# isolated_rs485.net
KiCad netlist of a schematic drawn in Altium Designer
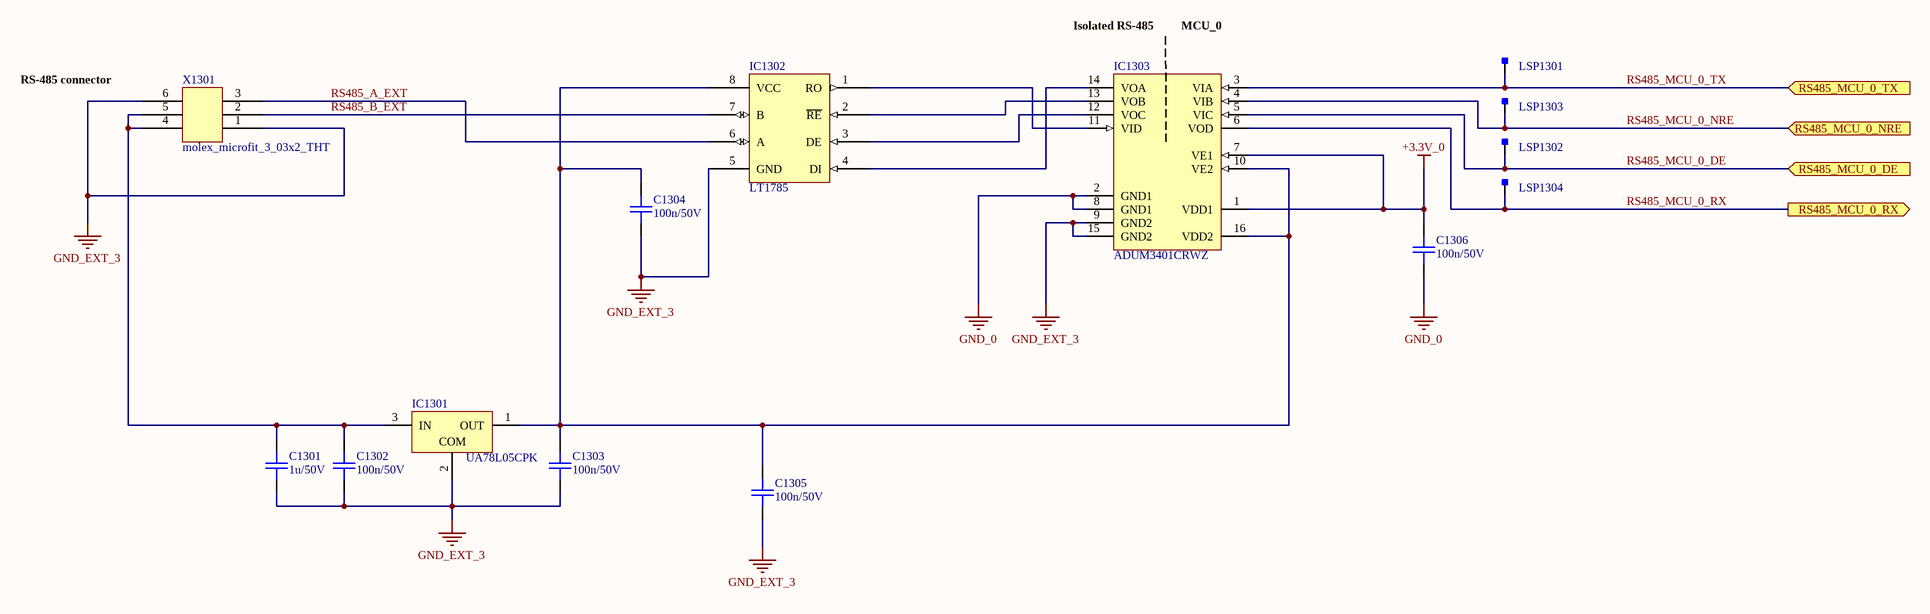
[diagram p0: isolated_rs485.SchDoc]

(export (version "E")
  (design (tool "Eeschema 10.0.6"))
  (components
    (comp (ref "C1301")
      (value "1u/50V")
      (footprint "CAPC1608X08N")
      (description "MLCC")
      (fields (field (name "PART NUMBER") "gen_C_ceramic_1u_50V_X7R_0603") (field (name "TOLERANCE") "± 10%"))
      (libsource (lib "OE750") (part "C"))
    )
    (comp (ref "C1302")
      (value "100n/50V")
      (footprint "CAPC1608X08N")
      (description "MLCC")
      (fields (field (name "PART NUMBER") "gen_C_ceramic_100n_50V_X7R_0603"))
      (libsource (lib "OE750") (part "C"))
    )
    (comp (ref "C1303")
      (value "100n/50V")
      (footprint "CAPC1608X08N")
      (description "MLCC")
      (fields (field (name "PART NUMBER") "gen_C_ceramic_100n_50V_X7R_0603"))
      (libsource (lib "OE750") (part "C"))
    )
    (comp (ref "C1304")
      (value "100n/50V")
      (footprint "CAPC1608X08N")
      (description "MLCC")
      (fields (field (name "PART NUMBER") "gen_C_ceramic_100n_50V_X7R_0603"))
      (libsource (lib "OE750") (part "C"))
    )
    (comp (ref "C1305")
      (value "100n/50V")
      (footprint "CAPC1608X08N")
      (description "MLCC")
      (fields (field (name "PART NUMBER") "gen_C_ceramic_100n_50V_X7R_0603"))
      (libsource (lib "OE750") (part "C"))
    )
    (comp (ref "C1306")
      (value "100n/50V")
      (footprint "CAPC1608X08N")
      (description "MLCC")
      (fields (field (name "PART NUMBER") "gen_C_ceramic_100n_50V_X7R_0603"))
      (libsource (lib "OE750") (part "C"))
    )
    (comp (ref "IC1301")
      (value "UA78L05CPK")
      (footprint "PK0003A_L")
      (fields (field (name "MANUFACTURER") "TexasInstruments"))
      (libsource (lib "Altium Content Vault") (part "TI-UA78L05-PK-3"))
    )
    (comp (ref "IC1302")
      (value "LT1785")
      (footprint "SOIC127P600X175-8N")
      (description "Transceiver RS422/RS485, Fault Protected, 4.75V-5.25V supply, SOIC-8")
      (fields (field (name "PART NUMBER") "LT1785CS8#PBF") (field (name "MANUFACTURER") "Linear Technology"))
      (libsource (lib "OE750") (part "LT1785"))
    )
    (comp (ref "IC1303")
      (value "ADUM3401CRWZ")
      (footprint "ADI-RW-16_N")
      (fields (field (name "MANUFACTURER") "Analog Devices"))
      (libsource (lib "Altium Content Vault") (part "ADI-ADUMX4X1-16"))
    )
    (comp (ref "LSP1301")
      (value "Testpoint_Square")
      (footprint "Testpoint_S1")
      (description "Testpoint, square")
      (libsource (lib "OE750") (part "Testpoint_Square"))
    )
    (comp (ref "LSP1302")
      (value "Testpoint_Square")
      (footprint "Testpoint_S1")
      (description "Testpoint, square")
      (libsource (lib "OE750") (part "Testpoint_Square"))
    )
    (comp (ref "LSP1303")
      (value "Testpoint_Square")
      (footprint "Testpoint_S1")
      (description "Testpoint, square")
      (libsource (lib "OE750") (part "Testpoint_Square"))
    )
    (comp (ref "LSP1304")
      (value "Testpoint_Square")
      (footprint "Testpoint_S1")
      (description "Testpoint, square")
      (libsource (lib "OE750") (part "Testpoint_Square"))
    )
    (comp (ref "X1301")
      (value "molex_microfit_3_03x2_THT")
      (footprint "MOLEX_MICROFIT_03x2_THT")
      (fields (field (name "MANUFACTURER") "Molex"))
      (libsource (lib "OE750") (part "X3x2"))
    )
  )
  (nets
    (net (code "1") (name "+3.3V_0") (class "Default")
      (node (ref "C1306") (pin "1") (pinfunction "1_1") (pintype "passive"))
      (node (ref "IC1303") (pin "1") (pinfunction "VDD1_1") (pintype "power_in"))
      (node (ref "IC1303") (pin "7") (pinfunction "VE1_7") (pintype "input"))
    )
    (net (code "2") (name "/RS485_A_EXT") (class "Default")
      (node (ref "IC1302") (pin "6") (pinfunction "A_6") (pintype "bidirectional"))
      (node (ref "X1301") (pin "3") (pintype "passive"))
    )
    (net (code "3") (name "/RS485_B_EXT") (class "Default")
      (node (ref "IC1302") (pin "7") (pinfunction "B_7") (pintype "bidirectional"))
      (node (ref "X1301") (pin "2") (pintype "passive"))
    )
    (net (code "4") (name "/RS485_MCU_0_DE") (class "Default")
      (node (ref "IC1303") (pin "5") (pinfunction "VIC_5") (pintype "input"))
      (node (ref "LSP1302") (pin "1") (pinfunction "1_1") (pintype "passive"))
    )
    (net (code "5") (name "/RS485_MCU_0_NRE") (class "Default")
      (node (ref "IC1303") (pin "4") (pinfunction "VIB_4") (pintype "input"))
      (node (ref "LSP1303") (pin "1") (pinfunction "1_1") (pintype "passive"))
    )
    (net (code "6") (name "/RS485_MCU_0_RX") (class "Default")
      (node (ref "IC1303") (pin "6") (pinfunction "VOD_6") (pintype "tri_state"))
      (node (ref "LSP1304") (pin "1") (pinfunction "1_1") (pintype "passive"))
    )
    (net (code "7") (name "/RS485_MCU_0_TX") (class "Default")
      (node (ref "IC1303") (pin "3") (pinfunction "VIA_3") (pintype "input"))
      (node (ref "LSP1301") (pin "1") (pinfunction "1_1") (pintype "passive"))
    )
    (net (code "8") (name "GND_0") (class "Default")
      (node (ref "C1306") (pin "2") (pinfunction "2_2") (pintype "passive"))
      (node (ref "IC1303") (pin "2") (pinfunction "GND1_2") (pintype "power_in"))
      (node (ref "IC1303") (pin "8") (pinfunction "GND1_8") (pintype "power_in"))
    )
    (net (code "9") (name "GND_EXT_3") (class "Default")
      (node (ref "C1301") (pin "2") (pinfunction "2_2") (pintype "passive"))
      (node (ref "C1302") (pin "2") (pinfunction "2_2") (pintype "passive"))
      (node (ref "C1303") (pin "2") (pinfunction "2_2") (pintype "passive"))
      (node (ref "C1304") (pin "2") (pinfunction "2_2") (pintype "passive"))
      (node (ref "C1305") (pin "2") (pinfunction "2_2") (pintype "passive"))
      (node (ref "IC1301") (pin "2") (pinfunction "COM_2") (pintype "power_in"))
      (node (ref "IC1302") (pin "5") (pinfunction "GND_5") (pintype "power_in"))
      (node (ref "IC1303") (pin "15") (pinfunction "GND2_15") (pintype "power_in"))
      (node (ref "IC1303") (pin "9") (pinfunction "GND2_9") (pintype "power_in"))
      (node (ref "X1301") (pin "1") (pintype "passive"))
      (node (ref "X1301") (pin "6") (pintype "passive"))
    )
    (net (code "10") (name "Net-(IC1301-IN)") (class "Default")
      (node (ref "C1301") (pin "1") (pinfunction "1_1") (pintype "passive"))
      (node (ref "C1302") (pin "1") (pinfunction "1_1") (pintype "passive"))
      (node (ref "IC1301") (pin "3") (pinfunction "IN_3") (pintype "power_in"))
      (node (ref "X1301") (pin "4") (pintype "passive"))
      (node (ref "X1301") (pin "5") (pintype "passive"))
    )
    (net (code "11") (name "Net-(IC1301-OUT)") (class "Default")
      (node (ref "C1303") (pin "1") (pinfunction "1_1") (pintype "passive"))
      (node (ref "C1304") (pin "1") (pinfunction "1_1") (pintype "passive"))
      (node (ref "C1305") (pin "1") (pinfunction "1_1") (pintype "passive"))
      (node (ref "IC1301") (pin "1") (pinfunction "OUT_1") (pintype "power_in"))
      (node (ref "IC1302") (pin "8") (pinfunction "VCC_8") (pintype "power_in"))
      (node (ref "IC1303") (pin "10") (pinfunction "VE2_10") (pintype "input"))
      (node (ref "IC1303") (pin "16") (pinfunction "VDD2_16") (pintype "power_in"))
    )
    (net (code "12") (name "Net-(IC1302-DE)") (class "Default")
      (node (ref "IC1302") (pin "3") (pinfunction "DE_3") (pintype "input"))
      (node (ref "IC1303") (pin "12") (pinfunction "VOC_12") (pintype "tri_state"))
    )
    (net (code "13") (name "Net-(IC1302-DI)") (class "Default")
      (node (ref "IC1302") (pin "4") (pinfunction "DI_4") (pintype "input"))
      (node (ref "IC1303") (pin "14") (pinfunction "VOA_14") (pintype "tri_state"))
    )
    (net (code "14") (name "Net-(IC1302-RO)") (class "Default")
      (node (ref "IC1302") (pin "1") (pinfunction "RO_1") (pintype "output"))
      (node (ref "IC1303") (pin "11") (pinfunction "VID_11") (pintype "input"))
    )
    (net (code "15") (name "Net-(IC1302-~{RE})") (class "Default")
      (node (ref "IC1302") (pin "2") (pinfunction "~{RE}_2") (pintype "input"))
      (node (ref "IC1303") (pin "13") (pinfunction "VOB_13") (pintype "tri_state"))
    )
  )
)
